# rev02_25.net
KiCad netlist of a schematic drawn in Altium Designer
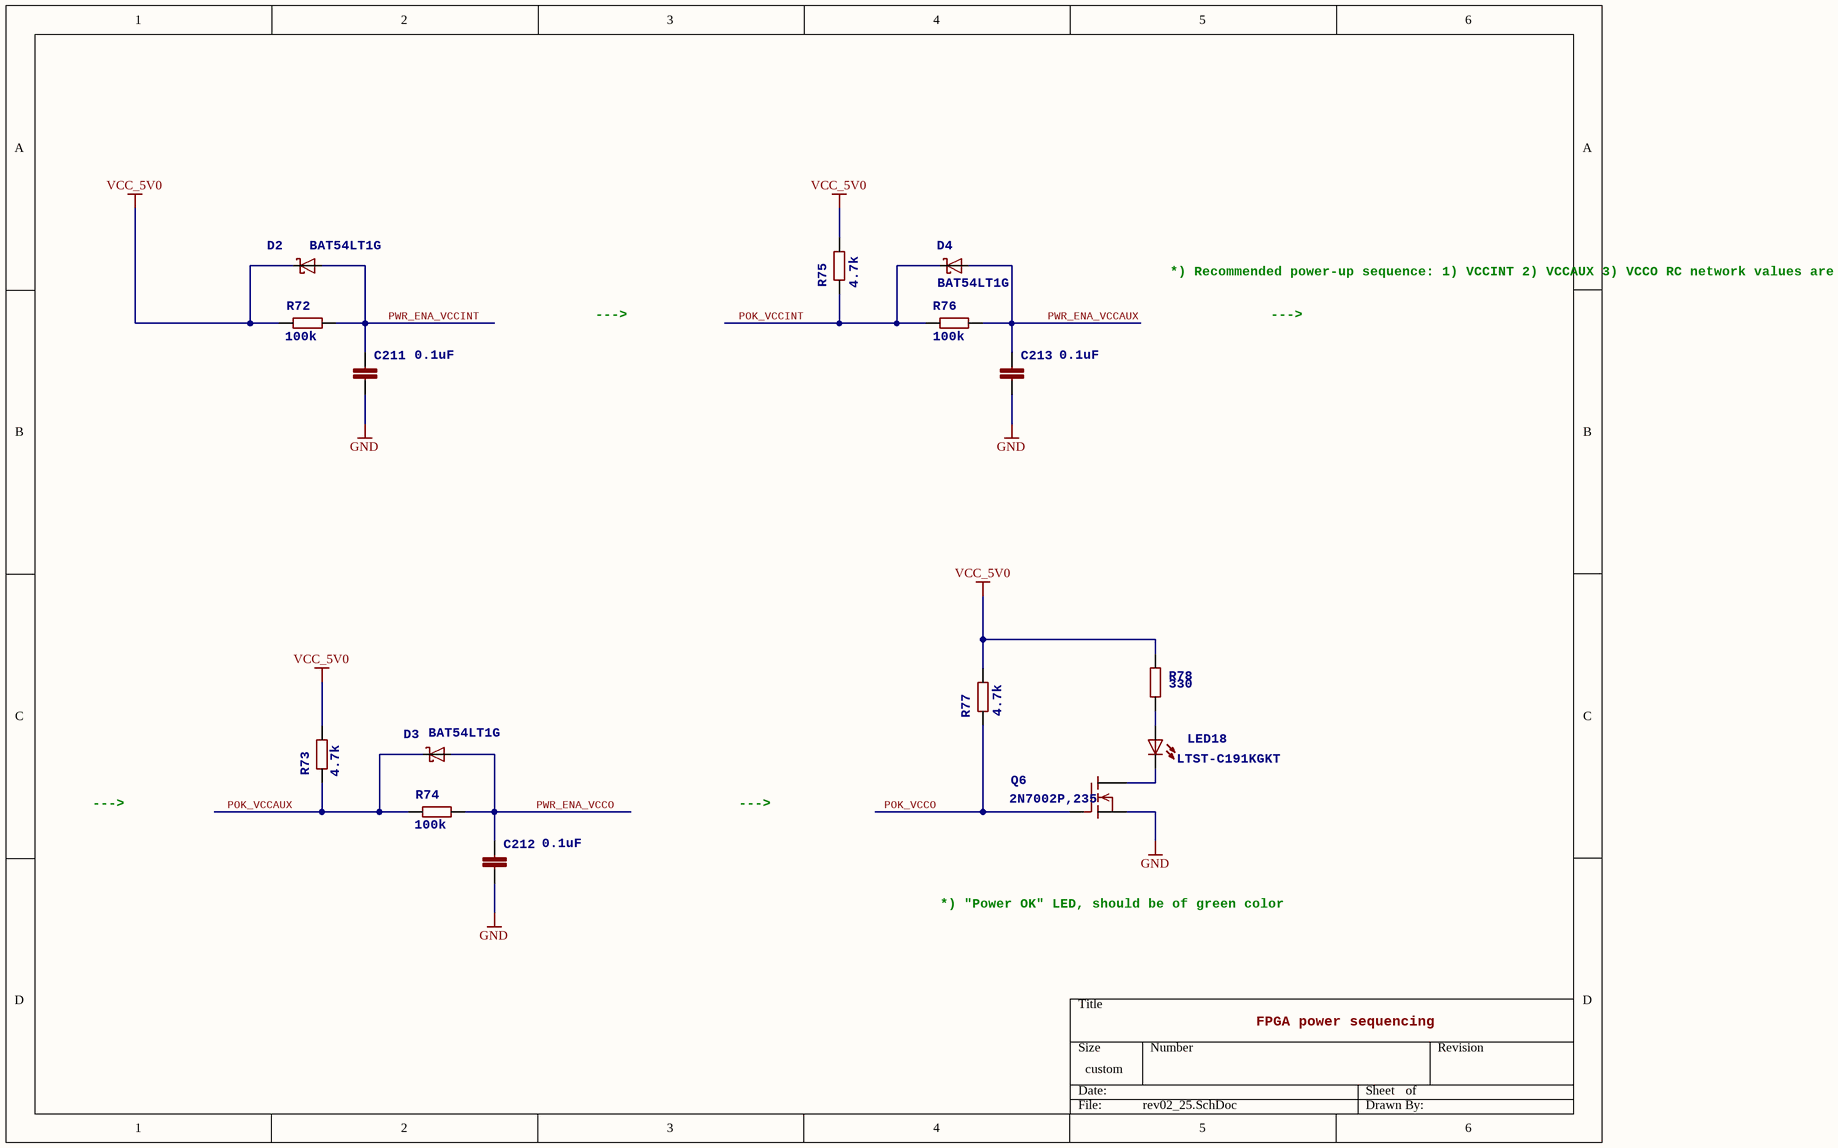
[diagram p0: rev02_25.SchDoc]

(export (version "E")
  (design (tool "Eeschema 10.0.6"))
  (components
    (comp (ref "C211")
      (value "0.1uF")
      (footprint "C_0402")
      (description "0402 CAPACITOR")
      (fields (field (name "TOLERANCE") "10%") (field (name ">NAME") "C211"))
      (libsource (lib "resistor") (part "C-EUC0402"))
    )
    (comp (ref "C212")
      (value "0.1uF")
      (footprint "C_0402")
      (description "0402 CAPACITOR")
      (fields (field (name "TOLERANCE") "10%") (field (name ">NAME") "C212"))
      (libsource (lib "resistor") (part "C-EUC0402"))
    )
    (comp (ref "C213")
      (value "0.1uF")
      (footprint "C_0402")
      (description "0402 CAPACITOR")
      (fields (field (name "TOLERANCE") "10%") (field (name ">NAME") "C213"))
      (libsource (lib "resistor") (part "C-EUC0402"))
    )
    (comp (ref "D2")
      (value "BAT54LT1G")
      (footprint "SOT-23")
      (description "OnSemi Schottky Diode")
      (fields (field (name ">NAME") "D2"))
      (libsource (lib "diode") (part "BAT54"))
    )
    (comp (ref "D3")
      (value "BAT54LT1G")
      (footprint "SOT-23")
      (description "OnSemi Schottky Diode")
      (fields (field (name ">NAME") "D3"))
      (libsource (lib "diode") (part "BAT54"))
    )
    (comp (ref "D4")
      (value "BAT54LT1G")
      (footprint "SOT-23")
      (description "OnSemi Schottky Diode")
      (fields (field (name ">NAME") "D4"))
      (libsource (lib "diode") (part "BAT54"))
    )
    (comp (ref "LED18")
      (value "LTST-C191KGKT")
      (footprint "VD_0603")
      (description "GREEN LED")
      (fields (field (name ">NAME") "LED18"))
      (libsource (lib "rev02_1") (part "LEDCHIP-LED0603"))
    )
    (comp (ref "Q6")
      (value "2N7002P,235")
      (footprint "SOT-23")
      (description "OnSemi FET")
      (fields (field (name ">NAME") "Q6"))
      (libsource (lib "transistors_gaui") (part "2N7002"))
    )
    (comp (ref "R72")
      (value "100k")
      (footprint "R_0402")
      (description "0402 Resistor 1%")
      (fields (field (name "TOLERANCE") "1%") (field (name ">NAME") "R72"))
      (libsource (lib "resistor") (part "R-EU_R0402"))
    )
    (comp (ref "R73")
      (value "4.7k")
      (footprint "R_0402")
      (description "0402 Resistor 5%")
      (fields (field (name "TOLERANCE") "5%") (field (name ">NAME") "R73"))
      (libsource (lib "resistor") (part "R-EU_R0402"))
    )
    (comp (ref "R74")
      (value "100k")
      (footprint "R_0402")
      (description "0402 Resistor 1%")
      (fields (field (name "TOLERANCE") "1%") (field (name ">NAME") "R74"))
      (libsource (lib "resistor") (part "R-EU_R0402"))
    )
    (comp (ref "R75")
      (value "4.7k")
      (footprint "R_0402")
      (description "0402 Resistor 5%")
      (fields (field (name "TOLERANCE") "5%") (field (name ">NAME") "R75"))
      (libsource (lib "resistor") (part "R-EU_R0402"))
    )
    (comp (ref "R76")
      (value "100k")
      (footprint "R_0402")
      (description "0402 Resistor 1%")
      (fields (field (name "TOLERANCE") "1%") (field (name ">NAME") "R76"))
      (libsource (lib "resistor") (part "R-EU_R0402"))
    )
    (comp (ref "R77")
      (value "4.7k")
      (footprint "R_0402")
      (description "0402 Resistor 5%")
      (fields (field (name "TOLERANCE") "5%") (field (name ">NAME") "R77"))
      (libsource (lib "resistor") (part "R-EU_R0402"))
    )
    (comp (ref "R78")
      (value "330")
      (footprint "R_0402")
      (description "0402 Resistor 5%")
      (fields (field (name "TOLERANCE") "5%") (field (name ">NAME") "R78"))
      (libsource (lib "resistor") (part "R-EU_R0402"))
    )
  )
  (nets
    (net (code "1") (name "/POK_VCCAUX") (class "Default")
      (node (ref "D3") (pin "3") (pinfunction "C_3") (pintype "passive"))
      (node (ref "R73") (pin "1") (pinfunction "1_1") (pintype "passive"))
      (node (ref "R74") (pin "1") (pinfunction "1_1") (pintype "passive"))
    )
    (net (code "2") (name "/POK_VCCINT") (class "Default")
      (node (ref "D4") (pin "3") (pinfunction "C_3") (pintype "passive"))
      (node (ref "R75") (pin "1") (pinfunction "1_1") (pintype "passive"))
      (node (ref "R76") (pin "1") (pinfunction "1_1") (pintype "passive"))
    )
    (net (code "3") (name "/POK_VCCO") (class "Default")
      (node (ref "Q6") (pin "1") (pinfunction "G_1") (pintype "passive"))
      (node (ref "R77") (pin "1") (pinfunction "1_1") (pintype "passive"))
    )
    (net (code "4") (name "/PWR_ENA_VCCAUX") (class "Default")
      (node (ref "C213") (pin "1") (pinfunction "1_1") (pintype "passive"))
      (node (ref "D4") (pin "1") (pinfunction "A_1") (pintype "passive"))
      (node (ref "R76") (pin "2") (pinfunction "2_2") (pintype "passive"))
    )
    (net (code "5") (name "/PWR_ENA_VCCINT") (class "Default")
      (node (ref "C211") (pin "1") (pinfunction "1_1") (pintype "passive"))
      (node (ref "D2") (pin "1") (pinfunction "A_1") (pintype "passive"))
      (node (ref "R72") (pin "2") (pinfunction "2_2") (pintype "passive"))
    )
    (net (code "6") (name "/PWR_ENA_VCCO") (class "Default")
      (node (ref "C212") (pin "1") (pinfunction "1_1") (pintype "passive"))
      (node (ref "D3") (pin "1") (pinfunction "A_1") (pintype "passive"))
      (node (ref "R74") (pin "2") (pinfunction "2_2") (pintype "passive"))
    )
    (net (code "7") (name "GND") (class "Default")
      (node (ref "C211") (pin "2") (pinfunction "2_2") (pintype "passive"))
      (node (ref "C212") (pin "2") (pinfunction "2_2") (pintype "passive"))
      (node (ref "C213") (pin "2") (pinfunction "2_2") (pintype "passive"))
      (node (ref "Q6") (pin "2") (pinfunction "S_2") (pintype "passive"))
    )
    (net (code "8") (name "Net-(LED18-A)") (class "Default")
      (node (ref "LED18") (pin "1") (pinfunction "A_1") (pintype "passive"))
      (node (ref "R78") (pin "1") (pinfunction "1_1") (pintype "passive"))
    )
    (net (code "9") (name "Net-(LED18-C)") (class "Default")
      (node (ref "LED18") (pin "2") (pinfunction "C_2") (pintype "passive"))
      (node (ref "Q6") (pin "3") (pinfunction "D_3") (pintype "passive"))
    )
    (net (code "10") (name "VCC_5V0") (class "Default")
      (node (ref "D2") (pin "3") (pinfunction "C_3") (pintype "passive"))
      (node (ref "R72") (pin "1") (pinfunction "1_1") (pintype "passive"))
      (node (ref "R73") (pin "2") (pinfunction "2_2") (pintype "passive"))
      (node (ref "R75") (pin "2") (pinfunction "2_2") (pintype "passive"))
      (node (ref "R77") (pin "2") (pinfunction "2_2") (pintype "passive"))
      (node (ref "R78") (pin "2") (pinfunction "2_2") (pintype "passive"))
    )
  )
)
